# M102A.net
KiCad netlist of a schematic drawn in EAGLE
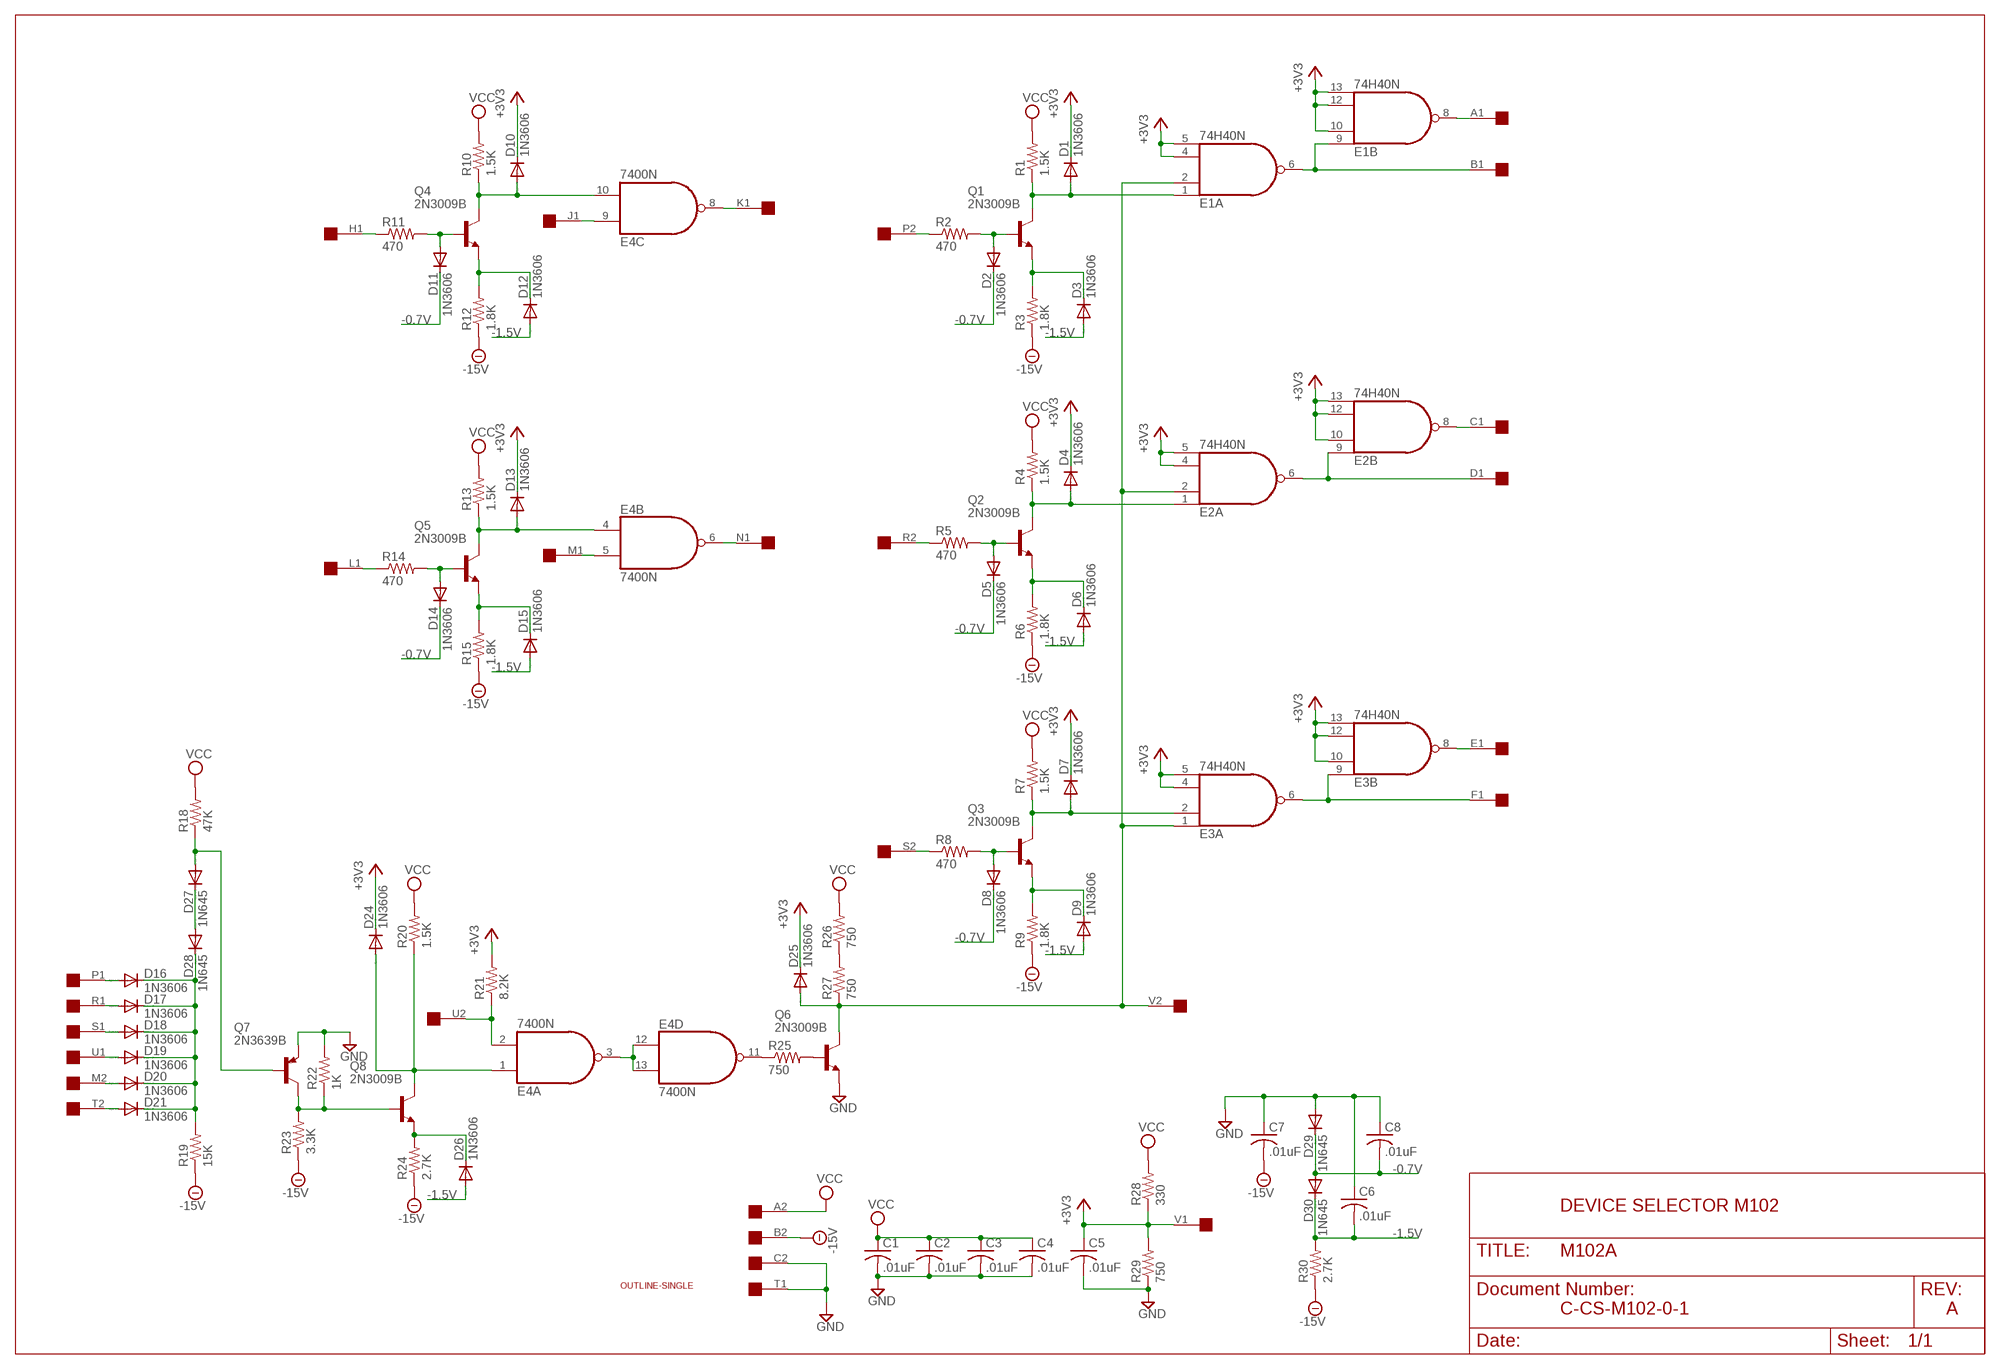
[diagram p0: schematic, sheet 1]

(export (version "E")
  (design (tool "Eeschema 10.0.6"))
  (components
    (comp (ref "C1")
      (value ".01uF")
      (footprint "eagle-import:C050-025X075")
      (libsource (lib "eagle-import") (part "C-US050-025X075"))
    )
    (comp (ref "C2")
      (value ".01uF")
      (footprint "eagle-import:C050-025X075")
      (libsource (lib "eagle-import") (part "C-US050-025X075"))
    )
    (comp (ref "C3")
      (value ".01uF")
      (footprint "eagle-import:C050-025X075")
      (libsource (lib "eagle-import") (part "C-US050-025X075"))
    )
    (comp (ref "C4")
      (value ".01uF")
      (footprint "eagle-import:C050-025X075")
      (libsource (lib "eagle-import") (part "C-US050-025X075"))
    )
    (comp (ref "C5")
      (value ".01uF")
      (footprint "eagle-import:C050-025X075")
      (libsource (lib "eagle-import") (part "C-US050-025X075"))
    )
    (comp (ref "C6")
      (value ".01uF")
      (footprint "eagle-import:C050-025X075")
      (libsource (lib "eagle-import") (part "C-US050-025X075"))
    )
    (comp (ref "C7")
      (value ".01uF")
      (footprint "eagle-import:C050-025X075")
      (libsource (lib "eagle-import") (part "C-US050-025X075"))
    )
    (comp (ref "C8")
      (value ".01uF")
      (footprint "eagle-import:C050-025X075")
      (libsource (lib "eagle-import") (part "C-US050-025X075"))
    )
    (comp (ref "D1")
      (value "1N3606")
      (footprint "eagle-import:DO35-10")
      (libsource (lib "eagle-import") (part "1N4148DO35-10"))
    )
    (comp (ref "D2")
      (value "1N3606")
      (footprint "eagle-import:DO35-10")
      (libsource (lib "eagle-import") (part "1N4148DO35-10"))
    )
    (comp (ref "D3")
      (value "1N3606")
      (footprint "eagle-import:DO35-10")
      (libsource (lib "eagle-import") (part "1N4148DO35-10"))
    )
    (comp (ref "D4")
      (value "1N3606")
      (footprint "eagle-import:DO35-10")
      (libsource (lib "eagle-import") (part "1N4148DO35-10"))
    )
    (comp (ref "D5")
      (value "1N3606")
      (footprint "eagle-import:DO35-10")
      (libsource (lib "eagle-import") (part "1N4148DO35-10"))
    )
    (comp (ref "D6")
      (value "1N3606")
      (footprint "eagle-import:DO35-10")
      (libsource (lib "eagle-import") (part "1N4148DO35-10"))
    )
    (comp (ref "D7")
      (value "1N3606")
      (footprint "eagle-import:DO35-10")
      (libsource (lib "eagle-import") (part "1N4148DO35-10"))
    )
    (comp (ref "D8")
      (value "1N3606")
      (footprint "eagle-import:DO35-10")
      (libsource (lib "eagle-import") (part "1N4148DO35-10"))
    )
    (comp (ref "D9")
      (value "1N3606")
      (footprint "eagle-import:DO35-10")
      (libsource (lib "eagle-import") (part "1N4148DO35-10"))
    )
    (comp (ref "D10")
      (value "1N3606")
      (footprint "eagle-import:DO35-10")
      (libsource (lib "eagle-import") (part "1N4148DO35-10"))
    )
    (comp (ref "D11")
      (value "1N3606")
      (footprint "eagle-import:DO35-10")
      (libsource (lib "eagle-import") (part "1N4148DO35-10"))
    )
    (comp (ref "D12")
      (value "1N3606")
      (footprint "eagle-import:DO35-10")
      (libsource (lib "eagle-import") (part "1N4148DO35-10"))
    )
    (comp (ref "D13")
      (value "1N3606")
      (footprint "eagle-import:DO35-10")
      (libsource (lib "eagle-import") (part "1N4148DO35-10"))
    )
    (comp (ref "D14")
      (value "1N3606")
      (footprint "eagle-import:DO35-10")
      (libsource (lib "eagle-import") (part "1N4148DO35-10"))
    )
    (comp (ref "D15")
      (value "1N3606")
      (footprint "eagle-import:DO35-10")
      (libsource (lib "eagle-import") (part "1N4148DO35-10"))
    )
    (comp (ref "D16")
      (value "1N3606")
      (footprint "eagle-import:DO35-10")
      (libsource (lib "eagle-import") (part "1N4148DO35-10"))
    )
    (comp (ref "D17")
      (value "1N3606")
      (footprint "eagle-import:DO35-10")
      (libsource (lib "eagle-import") (part "1N4148DO35-10"))
    )
    (comp (ref "D18")
      (value "1N3606")
      (footprint "eagle-import:DO35-10")
      (libsource (lib "eagle-import") (part "1N4148DO35-10"))
    )
    (comp (ref "D19")
      (value "1N3606")
      (footprint "eagle-import:DO35-10")
      (libsource (lib "eagle-import") (part "1N4148DO35-10"))
    )
    (comp (ref "D20")
      (value "1N3606")
      (footprint "eagle-import:DO35-10")
      (libsource (lib "eagle-import") (part "1N4148DO35-10"))
    )
    (comp (ref "D21")
      (value "1N3606")
      (footprint "eagle-import:DO35-10")
      (libsource (lib "eagle-import") (part "1N4148DO35-10"))
    )
    (comp (ref "D24")
      (value "1N3606")
      (footprint "eagle-import:DO35-10")
      (libsource (lib "eagle-import") (part "1N4148DO35-10"))
    )
    (comp (ref "D25")
      (value "1N3606")
      (footprint "eagle-import:DO35-10")
      (libsource (lib "eagle-import") (part "1N4148DO35-10"))
    )
    (comp (ref "D26")
      (value "1N3606")
      (footprint "eagle-import:DO35-10")
      (libsource (lib "eagle-import") (part "1N4148DO35-10"))
    )
    (comp (ref "D27")
      (value "1N645")
      (footprint "eagle-import:DO35-10")
      (libsource (lib "eagle-import") (part "1N4148DO35-10"))
    )
    (comp (ref "D28")
      (value "1N645")
      (footprint "eagle-import:DO35-10")
      (libsource (lib "eagle-import") (part "1N4148DO35-10"))
    )
    (comp (ref "D29")
      (value "1N645")
      (footprint "eagle-import:DO35-10")
      (libsource (lib "eagle-import") (part "1N4148DO35-10"))
    )
    (comp (ref "D30")
      (value "1N645")
      (footprint "eagle-import:DO35-10")
      (libsource (lib "eagle-import") (part "1N4148DO35-10"))
    )
    (comp (ref "E1")
      (value "74H40N")
      (footprint "eagle-import:DIL14")
      (libsource (lib "eagle-import") (part "7420NS"))
    )
    (comp (ref "E2")
      (value "74H40N")
      (footprint "eagle-import:DIL14")
      (libsource (lib "eagle-import") (part "7420NS"))
    )
    (comp (ref "E3")
      (value "74H40N")
      (footprint "eagle-import:DIL14")
      (libsource (lib "eagle-import") (part "7420NS"))
    )
    (comp (ref "E4")
      (value "7400N")
      (footprint "eagle-import:DIL14")
      (libsource (lib "eagle-import") (part "7400N"))
    )
    (comp (ref "Q1")
      (value "2N3009B")
      (footprint "eagle-import:TO39")
      (libsource (lib "eagle-import") (part "-NPN-TO39-EBC2N1613"))
    )
    (comp (ref "Q2")
      (value "2N3009B")
      (footprint "eagle-import:TO39")
      (libsource (lib "eagle-import") (part "-NPN-TO39-EBC2N1613"))
    )
    (comp (ref "Q3")
      (value "2N3009B")
      (footprint "eagle-import:TO39")
      (libsource (lib "eagle-import") (part "-NPN-TO39-EBC2N1613"))
    )
    (comp (ref "Q4")
      (value "2N3009B")
      (footprint "eagle-import:TO39")
      (libsource (lib "eagle-import") (part "-NPN-TO39-EBC2N1613"))
    )
    (comp (ref "Q5")
      (value "2N3009B")
      (footprint "eagle-import:TO39")
      (libsource (lib "eagle-import") (part "-NPN-TO39-EBC2N1613"))
    )
    (comp (ref "Q6")
      (value "2N3009B")
      (footprint "eagle-import:TO39")
      (libsource (lib "eagle-import") (part "-NPN-TO39-EBC2N1613"))
    )
    (comp (ref "Q7")
      (value "2N3639B")
      (footprint "eagle-import:TO39")
      (libsource (lib "eagle-import") (part "-PNP-TO39-EBC2N3635"))
    )
    (comp (ref "Q8")
      (value "2N3009B")
      (footprint "eagle-import:TO39")
      (libsource (lib "eagle-import") (part "-NPN-TO39-EBC2N1613"))
    )
    (comp (ref "R1")
      (value "1.5K")
      (footprint "eagle-import:0207_10")
      (libsource (lib "eagle-import") (part "R-US_0207/10"))
    )
    (comp (ref "R2")
      (value "470")
      (footprint "eagle-import:0207_10")
      (libsource (lib "eagle-import") (part "R-US_0207/10"))
    )
    (comp (ref "R3")
      (value "1.8K")
      (footprint "eagle-import:0207_10")
      (libsource (lib "eagle-import") (part "R-US_0207/10"))
    )
    (comp (ref "R4")
      (value "1.5K")
      (footprint "eagle-import:0207_10")
      (libsource (lib "eagle-import") (part "R-US_0207/10"))
    )
    (comp (ref "R5")
      (value "470")
      (footprint "eagle-import:0207_10")
      (libsource (lib "eagle-import") (part "R-US_0207/10"))
    )
    (comp (ref "R6")
      (value "1.8K")
      (footprint "eagle-import:0207_10")
      (libsource (lib "eagle-import") (part "R-US_0207/10"))
    )
    (comp (ref "R7")
      (value "1.5K")
      (footprint "eagle-import:0207_10")
      (libsource (lib "eagle-import") (part "R-US_0207/10"))
    )
    (comp (ref "R8")
      (value "470")
      (footprint "eagle-import:0207_10")
      (libsource (lib "eagle-import") (part "R-US_0207/10"))
    )
    (comp (ref "R9")
      (value "1.8K")
      (footprint "eagle-import:0207_10")
      (libsource (lib "eagle-import") (part "R-US_0207/10"))
    )
    (comp (ref "R10")
      (value "1.5K")
      (footprint "eagle-import:0207_10")
      (libsource (lib "eagle-import") (part "R-US_0207/10"))
    )
    (comp (ref "R11")
      (value "470")
      (footprint "eagle-import:0207_10")
      (libsource (lib "eagle-import") (part "R-US_0207/10"))
    )
    (comp (ref "R12")
      (value "1.8K")
      (footprint "eagle-import:0207_10")
      (libsource (lib "eagle-import") (part "R-US_0207/10"))
    )
    (comp (ref "R13")
      (value "1.5K")
      (footprint "eagle-import:0207_10")
      (libsource (lib "eagle-import") (part "R-US_0207/10"))
    )
    (comp (ref "R14")
      (value "470")
      (footprint "eagle-import:0207_10")
      (libsource (lib "eagle-import") (part "R-US_0207/10"))
    )
    (comp (ref "R15")
      (value "1.8K")
      (footprint "eagle-import:0207_10")
      (libsource (lib "eagle-import") (part "R-US_0207/10"))
    )
    (comp (ref "R18")
      (value "47K")
      (footprint "eagle-import:0207_10")
      (libsource (lib "eagle-import") (part "R-US_0207/10"))
    )
    (comp (ref "R19")
      (value "15K")
      (footprint "eagle-import:0207_10")
      (libsource (lib "eagle-import") (part "R-US_0207/10"))
    )
    (comp (ref "R20")
      (value "1.5K")
      (footprint "eagle-import:0207_10")
      (libsource (lib "eagle-import") (part "R-US_0207/10"))
    )
    (comp (ref "R21")
      (value "8.2K")
      (footprint "eagle-import:0207_10")
      (libsource (lib "eagle-import") (part "R-US_0207/10"))
    )
    (comp (ref "R22")
      (value "1K")
      (footprint "eagle-import:0207_10")
      (libsource (lib "eagle-import") (part "R-US_0207/10"))
    )
    (comp (ref "R23")
      (value "3.3K")
      (footprint "eagle-import:0207_10")
      (libsource (lib "eagle-import") (part "R-US_0207/10"))
    )
    (comp (ref "R24")
      (value "2.7K")
      (footprint "eagle-import:0207_10")
      (libsource (lib "eagle-import") (part "R-US_0207/10"))
    )
    (comp (ref "R25")
      (value "750")
      (footprint "eagle-import:0207_10")
      (libsource (lib "eagle-import") (part "R-US_0207/10"))
    )
    (comp (ref "R26")
      (value "750")
      (footprint "eagle-import:0207_10")
      (libsource (lib "eagle-import") (part "R-US_0207/10"))
    )
    (comp (ref "R27")
      (value "750")
      (footprint "eagle-import:0207_10")
      (libsource (lib "eagle-import") (part "R-US_0207/10"))
    )
    (comp (ref "R28")
      (value "330")
      (footprint "eagle-import:0207_10")
      (libsource (lib "eagle-import") (part "R-US_0207/10"))
    )
    (comp (ref "R29")
      (value "750")
      (footprint "eagle-import:0207_10")
      (libsource (lib "eagle-import") (part "R-US_0207/10"))
    )
    (comp (ref "R30")
      (value "2.7K")
      (footprint "eagle-import:0207_10")
      (libsource (lib "eagle-import") (part "R-US_0207/10"))
    )
    (comp (ref "U$8")
      (value "SINGLE")
      (footprint "eagle-import:EDGE-CON2")
      (libsource (lib "eagle-import") (part "SINGLE"))
    )
    (comp (ref "U$9")
      (value "OUTLINE-SINGLE")
      (footprint "eagle-import:SINGLE")
      (libsource (lib "eagle-import") (part "OUTLINE-SINGLE"))
    )
  )
  (nets
    (net (code "1") (name "+3V3") (class "Default")
      (node (ref "C5") (pin "1") (pinfunction "1_1") (pintype "passive"))
      (node (ref "D1") (pin "C") (pinfunction "C_C") (pintype "passive"))
      (node (ref "D10") (pin "C") (pinfunction "C_C") (pintype "passive"))
      (node (ref "D13") (pin "C") (pinfunction "C_C") (pintype "passive"))
      (node (ref "D24") (pin "C") (pinfunction "C_C") (pintype "passive"))
      (node (ref "D25") (pin "C") (pinfunction "C_C") (pintype "passive"))
      (node (ref "D4") (pin "C") (pinfunction "C_C") (pintype "passive"))
      (node (ref "D7") (pin "C") (pinfunction "C_C") (pintype "passive"))
      (node (ref "E1") (pin "10") (pinfunction "I1_10") (pintype "input"))
      (node (ref "E1") (pin "12") (pinfunction "I2_12") (pintype "input"))
      (node (ref "E1") (pin "13") (pinfunction "I3_13") (pintype "input"))
      (node (ref "E1") (pin "4") (pinfunction "I2_4") (pintype "input"))
      (node (ref "E1") (pin "5") (pinfunction "I3_5") (pintype "input"))
      (node (ref "E2") (pin "10") (pinfunction "I1_10") (pintype "input"))
      (node (ref "E2") (pin "12") (pinfunction "I2_12") (pintype "input"))
      (node (ref "E2") (pin "13") (pinfunction "I3_13") (pintype "input"))
      (node (ref "E2") (pin "4") (pinfunction "I2_4") (pintype "input"))
      (node (ref "E2") (pin "5") (pinfunction "I3_5") (pintype "input"))
      (node (ref "E3") (pin "10") (pinfunction "I1_10") (pintype "input"))
      (node (ref "E3") (pin "12") (pinfunction "I2_12") (pintype "input"))
      (node (ref "E3") (pin "13") (pinfunction "I3_13") (pintype "input"))
      (node (ref "E3") (pin "4") (pinfunction "I2_4") (pintype "input"))
      (node (ref "E3") (pin "5") (pinfunction "I3_5") (pintype "input"))
      (node (ref "R21") (pin "2") (pinfunction "2_2") (pintype "passive"))
      (node (ref "R28") (pin "1") (pinfunction "1_1") (pintype "passive"))
      (node (ref "R29") (pin "2") (pinfunction "2_2") (pintype "passive"))
      (node (ref "U$8") (pin "V1") (pinfunction "1_V1") (pintype "bidirectional"))
    )
    (net (code "2") (name "-15V") (class "Default")
      (node (ref "C7") (pin "2") (pinfunction "2_2") (pintype "passive"))
      (node (ref "R12") (pin "1") (pinfunction "1_1") (pintype "passive"))
      (node (ref "R15") (pin "1") (pinfunction "1_1") (pintype "passive"))
      (node (ref "R19") (pin "1") (pinfunction "1_1") (pintype "passive"))
      (node (ref "R23") (pin "1") (pinfunction "1_1") (pintype "passive"))
      (node (ref "R24") (pin "1") (pinfunction "1_1") (pintype "passive"))
      (node (ref "R3") (pin "1") (pinfunction "1_1") (pintype "passive"))
      (node (ref "R30") (pin "1") (pinfunction "1_1") (pintype "passive"))
      (node (ref "R6") (pin "1") (pinfunction "1_1") (pintype "passive"))
      (node (ref "R9") (pin "1") (pinfunction "1_1") (pintype "passive"))
      (node (ref "U$8") (pin "B2") (pinfunction "1_B2") (pintype "bidirectional"))
    )
    (net (code "3") (name "/-0.7V") (class "Default")
      (node (ref "C8") (pin "2") (pinfunction "2_2") (pintype "passive"))
      (node (ref "D11") (pin "C") (pinfunction "C_C") (pintype "passive"))
      (node (ref "D14") (pin "C") (pinfunction "C_C") (pintype "passive"))
      (node (ref "D2") (pin "C") (pinfunction "C_C") (pintype "passive"))
      (node (ref "D29") (pin "C") (pinfunction "C_C") (pintype "passive"))
      (node (ref "D30") (pin "A") (pinfunction "A_A") (pintype "passive"))
      (node (ref "D5") (pin "C") (pinfunction "C_C") (pintype "passive"))
      (node (ref "D8") (pin "C") (pinfunction "C_C") (pintype "passive"))
    )
    (net (code "4") (name "/-1.5V") (class "Default")
      (node (ref "C6") (pin "2") (pinfunction "2_2") (pintype "passive"))
      (node (ref "D12") (pin "A") (pinfunction "A_A") (pintype "passive"))
      (node (ref "D15") (pin "A") (pinfunction "A_A") (pintype "passive"))
      (node (ref "D26") (pin "A") (pinfunction "A_A") (pintype "passive"))
      (node (ref "D3") (pin "A") (pinfunction "A_A") (pintype "passive"))
      (node (ref "D30") (pin "C") (pinfunction "C_C") (pintype "passive"))
      (node (ref "D6") (pin "A") (pinfunction "A_A") (pintype "passive"))
      (node (ref "D9") (pin "A") (pinfunction "A_A") (pintype "passive"))
      (node (ref "R30") (pin "2") (pinfunction "2_2") (pintype "passive"))
    )
    (net (code "5") (name "GND") (class "Default")
      (node (ref "C1") (pin "2") (pinfunction "2_2") (pintype "passive"))
      (node (ref "C2") (pin "2") (pinfunction "2_2") (pintype "passive"))
      (node (ref "C3") (pin "2") (pinfunction "2_2") (pintype "passive"))
      (node (ref "C4") (pin "2") (pinfunction "2_2") (pintype "passive"))
      (node (ref "C5") (pin "2") (pinfunction "2_2") (pintype "passive"))
      (node (ref "C6") (pin "1") (pinfunction "1_1") (pintype "passive"))
      (node (ref "C7") (pin "1") (pinfunction "1_1") (pintype "passive"))
      (node (ref "C8") (pin "1") (pinfunction "1_1") (pintype "passive"))
      (node (ref "D29") (pin "A") (pinfunction "A_A") (pintype "passive"))
      (node (ref "Q6") (pin "1") (pinfunction "E_1") (pintype "passive"))
      (node (ref "Q7") (pin "1") (pinfunction "E_1") (pintype "passive"))
      (node (ref "R22") (pin "2") (pinfunction "2_2") (pintype "passive"))
      (node (ref "R29") (pin "1") (pinfunction "1_1") (pintype "passive"))
      (node (ref "U$8") (pin "C2") (pinfunction "1_C2") (pintype "bidirectional"))
      (node (ref "U$8") (pin "T1") (pinfunction "1_T1") (pintype "bidirectional"))
    )
    (net (code "6") (name "Net-(D16-PadC)") (class "Default")
      (node (ref "D16") (pin "C") (pinfunction "C_C") (pintype "passive"))
      (node (ref "D17") (pin "C") (pinfunction "C_C") (pintype "passive"))
      (node (ref "D18") (pin "C") (pinfunction "C_C") (pintype "passive"))
      (node (ref "D19") (pin "C") (pinfunction "C_C") (pintype "passive"))
      (node (ref "D20") (pin "C") (pinfunction "C_C") (pintype "passive"))
      (node (ref "D21") (pin "C") (pinfunction "C_C") (pintype "passive"))
      (node (ref "D28") (pin "C") (pinfunction "C_C") (pintype "passive"))
      (node (ref "R19") (pin "2") (pinfunction "2_2") (pintype "passive"))
    )
    (net (code "7") (name "Net-(D27-PadC)") (class "Default")
      (node (ref "D27") (pin "C") (pinfunction "C_C") (pintype "passive"))
      (node (ref "D28") (pin "A") (pinfunction "A_A") (pintype "passive"))
    )
    (net (code "8") (name "Net-(E1A-I0)") (class "Default")
      (node (ref "D1") (pin "A") (pinfunction "A_A") (pintype "passive"))
      (node (ref "E1") (pin "1") (pinfunction "I0_1") (pintype "input"))
      (node (ref "Q1") (pin "3") (pinfunction "C_3") (pintype "passive"))
      (node (ref "R1") (pin "1") (pinfunction "1_1") (pintype "passive"))
    )
    (net (code "9") (name "Net-(E1A-I1)") (class "Default")
      (node (ref "D25") (pin "A") (pinfunction "A_A") (pintype "passive"))
      (node (ref "E1") (pin "2") (pinfunction "I1_2") (pintype "input"))
      (node (ref "E2") (pin "2") (pinfunction "I1_2") (pintype "input"))
      (node (ref "E3") (pin "1") (pinfunction "I0_1") (pintype "input"))
      (node (ref "Q6") (pin "3") (pinfunction "C_3") (pintype "passive"))
      (node (ref "R27") (pin "1") (pinfunction "1_1") (pintype "passive"))
      (node (ref "U$8") (pin "V2") (pinfunction "1_V2") (pintype "bidirectional"))
    )
    (net (code "10") (name "Net-(E1A-O)") (class "Default")
      (node (ref "E1") (pin "6") (pinfunction "O_6") (pintype "output"))
      (node (ref "E1") (pin "9") (pinfunction "I0_9") (pintype "input"))
      (node (ref "U$8") (pin "B1") (pinfunction "1_B1") (pintype "bidirectional"))
    )
    (net (code "11") (name "Net-(E1B-O)") (class "Default")
      (node (ref "E1") (pin "8") (pinfunction "O_8") (pintype "output"))
      (node (ref "U$8") (pin "A1") (pinfunction "1_A1") (pintype "bidirectional"))
    )
    (net (code "12") (name "Net-(E2A-I0)") (class "Default")
      (node (ref "D4") (pin "A") (pinfunction "A_A") (pintype "passive"))
      (node (ref "E2") (pin "1") (pinfunction "I0_1") (pintype "input"))
      (node (ref "Q2") (pin "3") (pinfunction "C_3") (pintype "passive"))
      (node (ref "R4") (pin "1") (pinfunction "1_1") (pintype "passive"))
    )
    (net (code "13") (name "Net-(E2A-O)") (class "Default")
      (node (ref "E2") (pin "6") (pinfunction "O_6") (pintype "output"))
      (node (ref "E2") (pin "9") (pinfunction "I0_9") (pintype "input"))
      (node (ref "U$8") (pin "D1") (pinfunction "1_D1") (pintype "bidirectional"))
    )
    (net (code "14") (name "Net-(E2B-O)") (class "Default")
      (node (ref "E2") (pin "8") (pinfunction "O_8") (pintype "output"))
      (node (ref "U$8") (pin "C1") (pinfunction "1_C1") (pintype "bidirectional"))
    )
    (net (code "15") (name "Net-(E3A-I1)") (class "Default")
      (node (ref "D7") (pin "A") (pinfunction "A_A") (pintype "passive"))
      (node (ref "E3") (pin "2") (pinfunction "I1_2") (pintype "input"))
      (node (ref "Q3") (pin "3") (pinfunction "C_3") (pintype "passive"))
      (node (ref "R7") (pin "1") (pinfunction "1_1") (pintype "passive"))
    )
    (net (code "16") (name "Net-(E3A-O)") (class "Default")
      (node (ref "E3") (pin "6") (pinfunction "O_6") (pintype "output"))
      (node (ref "E3") (pin "9") (pinfunction "I0_9") (pintype "input"))
      (node (ref "U$8") (pin "F1") (pinfunction "1_F1") (pintype "bidirectional"))
    )
    (net (code "17") (name "Net-(E3B-O)") (class "Default")
      (node (ref "E3") (pin "8") (pinfunction "O_8") (pintype "output"))
      (node (ref "U$8") (pin "E1") (pinfunction "1_E1") (pintype "bidirectional"))
    )
    (net (code "18") (name "Net-(E4A-I0)") (class "Default")
      (node (ref "D24") (pin "A") (pinfunction "A_A") (pintype "passive"))
      (node (ref "E4") (pin "1") (pinfunction "I0_1") (pintype "input"))
      (node (ref "Q8") (pin "3") (pinfunction "C_3") (pintype "passive"))
      (node (ref "R20") (pin "1") (pinfunction "1_1") (pintype "passive"))
    )
    (net (code "19") (name "Net-(E4A-I1)") (class "Default")
      (node (ref "E4") (pin "2") (pinfunction "I1_2") (pintype "input"))
      (node (ref "R21") (pin "1") (pinfunction "1_1") (pintype "passive"))
      (node (ref "U$8") (pin "U2") (pinfunction "1_U2") (pintype "bidirectional"))
    )
    (net (code "20") (name "Net-(E4A-O)") (class "Default")
      (node (ref "E4") (pin "12") (pinfunction "I0_12") (pintype "input"))
      (node (ref "E4") (pin "13") (pinfunction "I1_13") (pintype "input"))
      (node (ref "E4") (pin "3") (pinfunction "O_3") (pintype "output"))
    )
    (net (code "21") (name "Net-(E4B-I0)") (class "Default")
      (node (ref "D13") (pin "A") (pinfunction "A_A") (pintype "passive"))
      (node (ref "E4") (pin "4") (pinfunction "I0_4") (pintype "input"))
      (node (ref "Q5") (pin "3") (pinfunction "C_3") (pintype "passive"))
      (node (ref "R13") (pin "1") (pinfunction "1_1") (pintype "passive"))
    )
    (net (code "22") (name "Net-(E4B-I1)") (class "Default")
      (node (ref "E4") (pin "5") (pinfunction "I1_5") (pintype "input"))
      (node (ref "U$8") (pin "M1") (pinfunction "1_M1") (pintype "bidirectional"))
    )
    (net (code "23") (name "Net-(E4B-O)") (class "Default")
      (node (ref "E4") (pin "6") (pinfunction "O_6") (pintype "output"))
      (node (ref "U$8") (pin "N1") (pinfunction "1_N1") (pintype "bidirectional"))
    )
    (net (code "24") (name "Net-(E4C-I0)") (class "Default")
      (node (ref "E4") (pin "9") (pinfunction "I0_9") (pintype "input"))
      (node (ref "U$8") (pin "J1") (pinfunction "1_J1") (pintype "bidirectional"))
    )
    (net (code "25") (name "Net-(E4C-I1)") (class "Default")
      (node (ref "D10") (pin "A") (pinfunction "A_A") (pintype "passive"))
      (node (ref "E4") (pin "10") (pinfunction "I1_10") (pintype "input"))
      (node (ref "Q4") (pin "3") (pinfunction "C_3") (pintype "passive"))
      (node (ref "R10") (pin "1") (pinfunction "1_1") (pintype "passive"))
    )
    (net (code "26") (name "Net-(E4C-O)") (class "Default")
      (node (ref "E4") (pin "8") (pinfunction "O_8") (pintype "output"))
      (node (ref "U$8") (pin "K1") (pinfunction "1_K1") (pintype "bidirectional"))
    )
    (net (code "27") (name "Net-(E4D-O)") (class "Default")
      (node (ref "E4") (pin "11") (pinfunction "O_11") (pintype "output"))
      (node (ref "R25") (pin "1") (pinfunction "1_1") (pintype "passive"))
    )
    (net (code "28") (name "Net-(Q1-B)") (class "Default")
      (node (ref "D2") (pin "A") (pinfunction "A_A") (pintype "passive"))
      (node (ref "Q1") (pin "2") (pinfunction "B_2") (pintype "passive"))
      (node (ref "R2") (pin "2") (pinfunction "2_2") (pintype "passive"))
    )
    (net (code "29") (name "Net-(Q1-E)") (class "Default")
      (node (ref "D3") (pin "C") (pinfunction "C_C") (pintype "passive"))
      (node (ref "Q1") (pin "1") (pinfunction "E_1") (pintype "passive"))
      (node (ref "R3") (pin "2") (pinfunction "2_2") (pintype "passive"))
    )
    (net (code "30") (name "Net-(Q2-B)") (class "Default")
      (node (ref "D5") (pin "A") (pinfunction "A_A") (pintype "passive"))
      (node (ref "Q2") (pin "2") (pinfunction "B_2") (pintype "passive"))
      (node (ref "R5") (pin "2") (pinfunction "2_2") (pintype "passive"))
    )
    (net (code "31") (name "Net-(Q2-E)") (class "Default")
      (node (ref "D6") (pin "C") (pinfunction "C_C") (pintype "passive"))
      (node (ref "Q2") (pin "1") (pinfunction "E_1") (pintype "passive"))
      (node (ref "R6") (pin "2") (pinfunction "2_2") (pintype "passive"))
    )
    (net (code "32") (name "Net-(Q3-B)") (class "Default")
      (node (ref "D8") (pin "A") (pinfunction "A_A") (pintype "passive"))
      (node (ref "Q3") (pin "2") (pinfunction "B_2") (pintype "passive"))
      (node (ref "R8") (pin "2") (pinfunction "2_2") (pintype "passive"))
    )
    (net (code "33") (name "Net-(Q3-E)") (class "Default")
      (node (ref "D9") (pin "C") (pinfunction "C_C") (pintype "passive"))
      (node (ref "Q3") (pin "1") (pinfunction "E_1") (pintype "passive"))
      (node (ref "R9") (pin "2") (pinfunction "2_2") (pintype "passive"))
    )
    (net (code "34") (name "Net-(Q4-B)") (class "Default")
      (node (ref "D11") (pin "A") (pinfunction "A_A") (pintype "passive"))
      (node (ref "Q4") (pin "2") (pinfunction "B_2") (pintype "passive"))
      (node (ref "R11") (pin "2") (pinfunction "2_2") (pintype "passive"))
    )
    (net (code "35") (name "Net-(Q4-E)") (class "Default")
      (node (ref "D12") (pin "C") (pinfunction "C_C") (pintype "passive"))
      (node (ref "Q4") (pin "1") (pinfunction "E_1") (pintype "passive"))
      (node (ref "R12") (pin "2") (pinfunction "2_2") (pintype "passive"))
    )
    (net (code "36") (name "Net-(Q5-B)") (class "Default")
      (node (ref "D14") (pin "A") (pinfunction "A_A") (pintype "passive"))
      (node (ref "Q5") (pin "2") (pinfunction "B_2") (pintype "passive"))
      (node (ref "R14") (pin "2") (pinfunction "2_2") (pintype "passive"))
    )
    (net (code "37") (name "Net-(Q5-E)") (class "Default")
      (node (ref "D15") (pin "C") (pinfunction "C_C") (pintype "passive"))
      (node (ref "Q5") (pin "1") (pinfunction "E_1") (pintype "passive"))
      (node (ref "R15") (pin "2") (pinfunction "2_2") (pintype "passive"))
    )
    (net (code "38") (name "Net-(Q6-B)") (class "Default")
      (node (ref "Q6") (pin "2") (pinfunction "B_2") (pintype "passive"))
      (node (ref "R25") (pin "2") (pinfunction "2_2") (pintype "passive"))
    )
    (net (code "39") (name "Net-(Q7-B)") (class "Default")
      (node (ref "D27") (pin "A") (pinfunction "A_A") (pintype "passive"))
      (node (ref "Q7") (pin "2") (pinfunction "B_2") (pintype "passive"))
      (node (ref "R18") (pin "1") (pinfunction "1_1") (pintype "passive"))
    )
    (net (code "40") (name "Net-(Q7-C)") (class "Default")
      (node (ref "Q7") (pin "3") (pinfunction "C_3") (pintype "passive"))
      (node (ref "Q8") (pin "2") (pinfunction "B_2") (pintype "passive"))
      (node (ref "R22") (pin "1") (pinfunction "1_1") (pintype "passive"))
      (node (ref "R23") (pin "2") (pinfunction "2_2") (pintype "passive"))
    )
    (net (code "41") (name "Net-(Q8-E)") (class "Default")
      (node (ref "D26") (pin "C") (pinfunction "C_C") (pintype "passive"))
      (node (ref "Q8") (pin "1") (pinfunction "E_1") (pintype "passive"))
      (node (ref "R24") (pin "2") (pinfunction "2_2") (pintype "passive"))
    )
    (net (code "42") (name "Net-(R26-Pad1)") (class "Default")
      (node (ref "R26") (pin "1") (pinfunction "1_1") (pintype "passive"))
      (node (ref "R27") (pin "2") (pinfunction "2_2") (pintype "passive"))
    )
    (net (code "43") (name "Net-(U$8AA-1)") (class "Default")
      (node (ref "D17") (pin "A") (pinfunction "A_A") (pintype "passive"))
      (node (ref "U$8") (pin "R1") (pinfunction "1_R1") (pintype "bidirectional"))
    )
    (net (code "44") (name "Net-(U$8AB-1)") (class "Default")
      (node (ref "R5") (pin "1") (pinfunction "1_1") (pintype "passive"))
      (node (ref "U$8") (pin "R2") (pinfunction "1_R2") (pintype "bidirectional"))
    )
    (net (code "45") (name "Net-(U$8AC-1)") (class "Default")
      (node (ref "D18") (pin "A") (pinfunction "A_A") (pintype "passive"))
      (node (ref "U$8") (pin "S1") (pinfunction "1_S1") (pintype "bidirectional"))
    )
    (net (code "46") (name "Net-(U$8AD-1)") (class "Default")
      (node (ref "R8") (pin "1") (pinfunction "1_1") (pintype "passive"))
      (node (ref "U$8") (pin "S2") (pinfunction "1_S2") (pintype "bidirectional"))
    )
    (net (code "47") (name "Net-(U$8AF-1)") (class "Default")
      (node (ref "D21") (pin "A") (pinfunction "A_A") (pintype "passive"))
      (node (ref "U$8") (pin "T2") (pinfunction "1_T2") (pintype "bidirectional"))
    )
    (net (code "48") (name "Net-(U$8AG-1)") (class "Default")
      (node (ref "D19") (pin "A") (pinfunction "A_A") (pintype "passive"))
      (node (ref "U$8") (pin "U1") (pinfunction "1_U1") (pintype "bidirectional"))
    )
    (net (code "49") (name "Net-(U$8M-1)") (class "Default")
      (node (ref "R11") (pin "1") (pinfunction "1_1") (pintype "passive"))
      (node (ref "U$8") (pin "H1") (pinfunction "1_H1") (pintype "bidirectional"))
    )
    (net (code "50") (name "Net-(U$8S-1)") (class "Default")
      (node (ref "R14") (pin "1") (pinfunction "1_1") (pintype "passive"))
      (node (ref "U$8") (pin "L1") (pinfunction "1_L1") (pintype "bidirectional"))
    )
    (net (code "51") (name "Net-(U$8V-1)") (class "Default")
      (node (ref "D20") (pin "A") (pinfunction "A_A") (pintype "passive"))
      (node (ref "U$8") (pin "M2") (pinfunction "1_M2") (pintype "bidirectional"))
    )
    (net (code "52") (name "Net-(U$8Y-1)") (class "Default")
      (node (ref "D16") (pin "A") (pinfunction "A_A") (pintype "passive"))
      (node (ref "U$8") (pin "P1") (pinfunction "1_P1") (pintype "bidirectional"))
    )
    (net (code "53") (name "Net-(U$8Z-1)") (class "Default")
      (node (ref "R2") (pin "1") (pinfunction "1_1") (pintype "passive"))
      (node (ref "U$8") (pin "P2") (pinfunction "1_P2") (pintype "bidirectional"))
    )
    (net (code "54") (name "VCC") (class "Default")
      (node (ref "C1") (pin "1") (pinfunction "1_1") (pintype "passive"))
      (node (ref "C2") (pin "1") (pinfunction "1_1") (pintype "passive"))
      (node (ref "C3") (pin "1") (pinfunction "1_1") (pintype "passive"))
      (node (ref "C4") (pin "1") (pinfunction "1_1") (pintype "passive"))
      (node (ref "R1") (pin "2") (pinfunction "2_2") (pintype "passive"))
      (node (ref "R10") (pin "2") (pinfunction "2_2") (pintype "passive"))
      (node (ref "R13") (pin "2") (pinfunction "2_2") (pintype "passive"))
      (node (ref "R18") (pin "2") (pinfunction "2_2") (pintype "passive"))
      (node (ref "R20") (pin "2") (pinfunction "2_2") (pintype "passive"))
      (node (ref "R26") (pin "2") (pinfunction "2_2") (pintype "passive"))
      (node (ref "R28") (pin "2") (pinfunction "2_2") (pintype "passive"))
      (node (ref "R4") (pin "2") (pinfunction "2_2") (pintype "passive"))
      (node (ref "R7") (pin "2") (pinfunction "2_2") (pintype "passive"))
      (node (ref "U$8") (pin "A2") (pinfunction "1_A2") (pintype "bidirectional"))
    )
  )
)
